# SOC_Power.net
KiCad netlist of a schematic drawn in Altium Designer
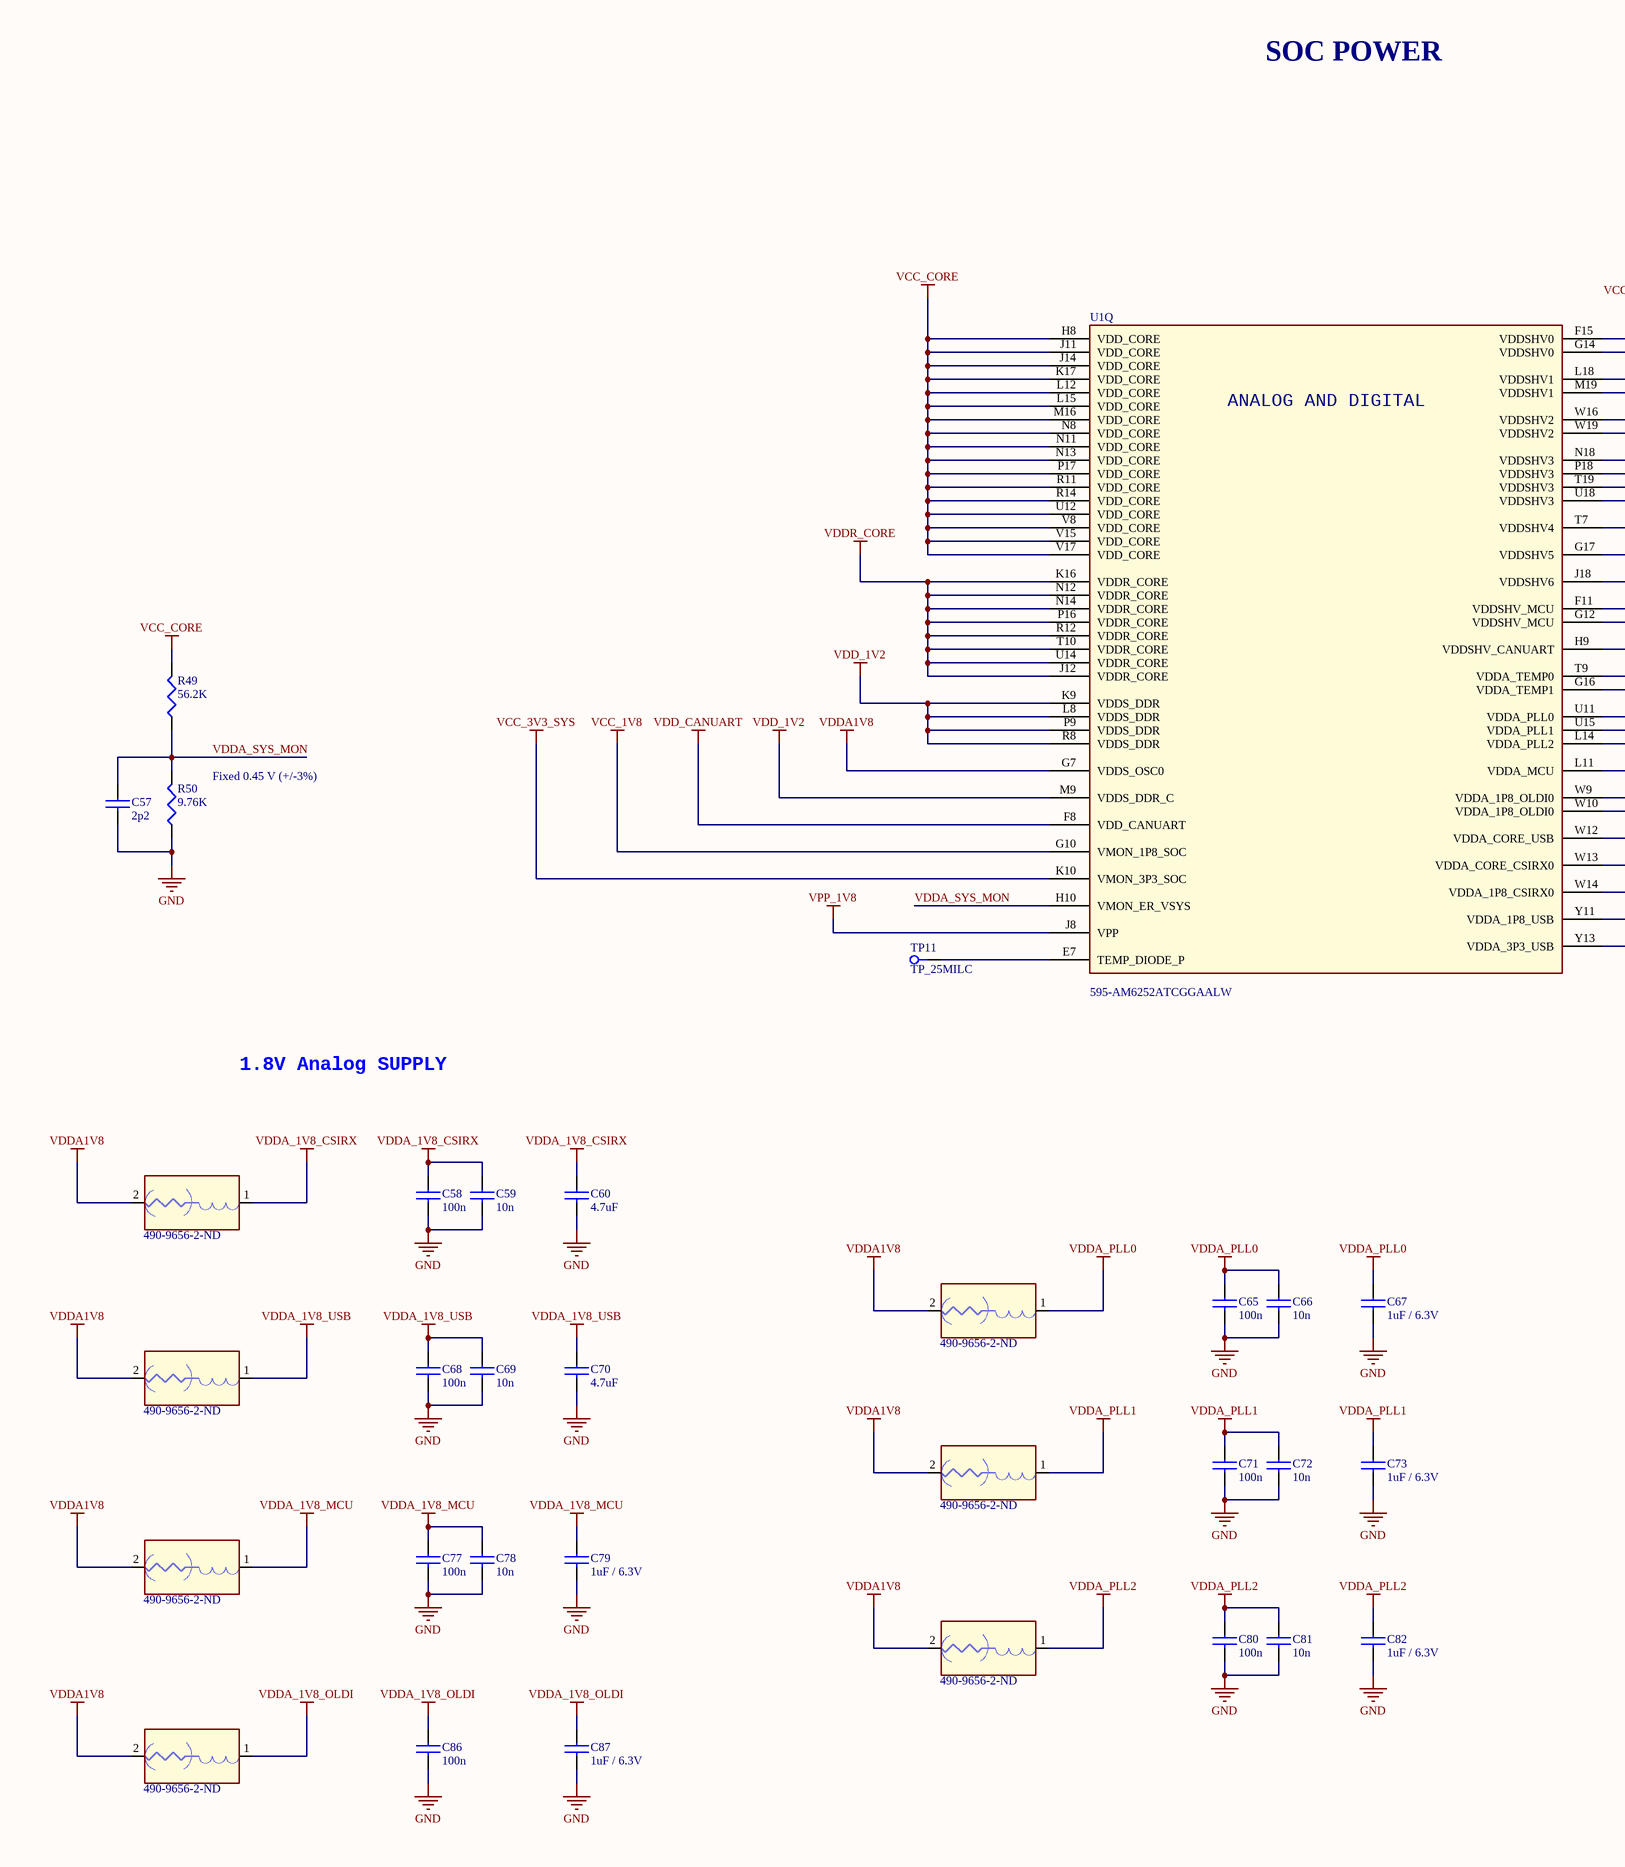
[diagram p0: SOC Power.SchDoc, left]
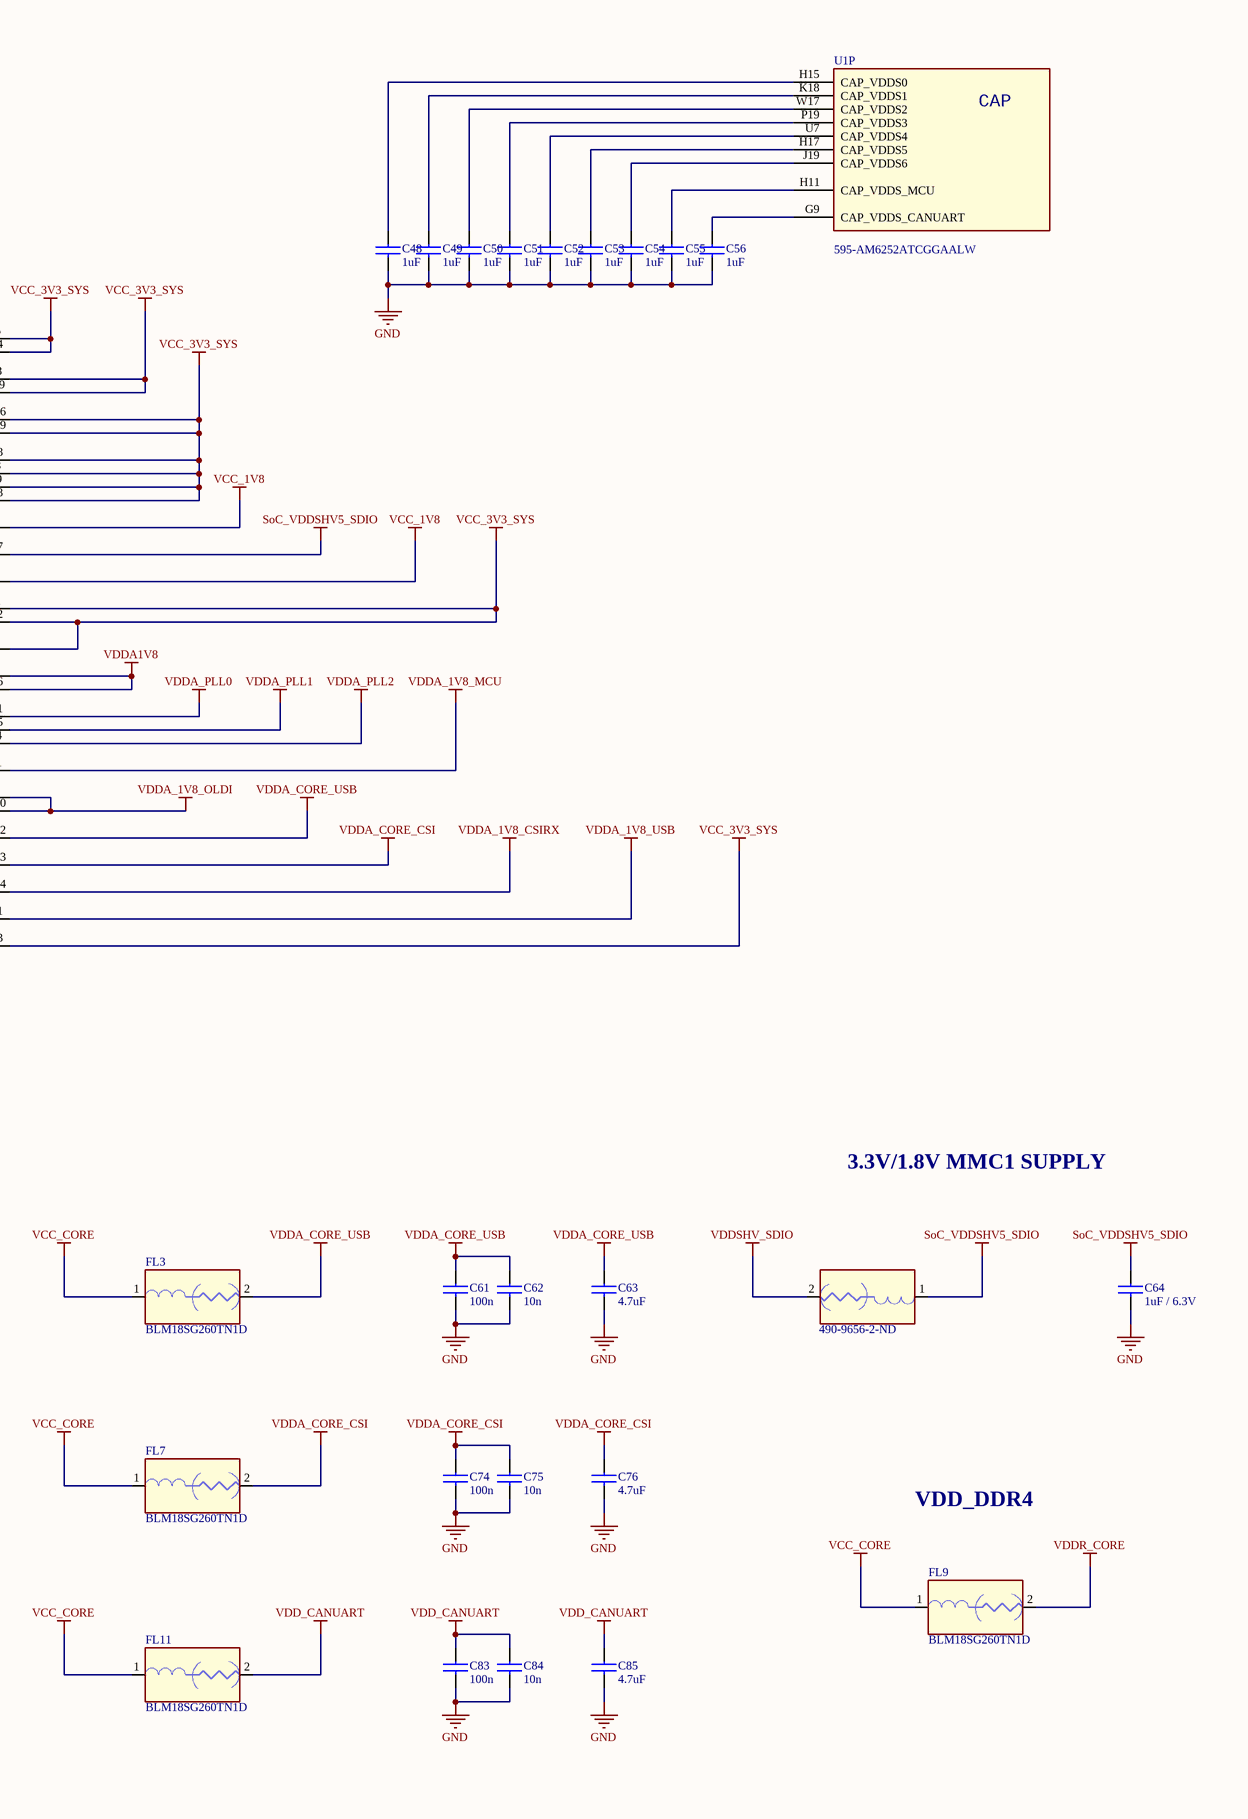
[diagram p1: SOC Power.SchDoc, right]

(export (version "E")
  (design (tool "Eeschema 10.0.6"))
  (components
    (comp (ref "C48")
      (value "1uF")
      (footprint "C0201")
      (description "CAP CER 1UF 6.3V X5R 0201")
      (fields
        (field (name "MANUFACTURER") "Samsung")
        (field (name "MANUFACTURER PART NUMBER") "CL03A105KQ3CSNC")
      )
      (libsource (lib "Schlib AM625") (part "CL03A105KQ3CSNC"))
    )
    (comp (ref "C49")
      (value "1uF")
      (footprint "C0201")
      (description "CAP CER 1UF 6.3V X5R 0201")
      (fields
        (field (name "MANUFACTURER") "Samsung")
        (field (name "MANUFACTURER PART NUMBER") "CL03A105KQ3CSNC")
      )
      (libsource (lib "Schlib AM625") (part "CL03A105KQ3CSNC"))
    )
    (comp (ref "C50")
      (value "1uF")
      (footprint "C0201")
      (description "CAP CER 1UF 6.3V X5R 0201")
      (fields
        (field (name "MANUFACTURER") "Samsung")
        (field (name "MANUFACTURER PART NUMBER") "CL03A105KQ3CSNC")
      )
      (libsource (lib "Schlib AM625") (part "CL03A105KQ3CSNC"))
    )
    (comp (ref "C51")
      (value "1uF")
      (footprint "C0201")
      (description "CAP CER 1UF 6.3V X5R 0201")
      (fields
        (field (name "MANUFACTURER") "Samsung")
        (field (name "MANUFACTURER PART NUMBER") "CL03A105KQ3CSNC")
      )
      (libsource (lib "Schlib AM625") (part "CL03A105KQ3CSNC"))
    )
    (comp (ref "C52")
      (value "1uF")
      (footprint "C0201")
      (description "CAP CER 1UF 6.3V X5R 0201")
      (fields
        (field (name "MANUFACTURER") "Samsung")
        (field (name "MANUFACTURER PART NUMBER") "CL03A105KQ3CSNC")
      )
      (libsource (lib "Schlib AM625") (part "CL03A105KQ3CSNC"))
    )
    (comp (ref "C53")
      (value "1uF")
      (footprint "C0201")
      (description "CAP CER 1UF 6.3V X5R 0201")
      (fields
        (field (name "MANUFACTURER") "Samsung")
        (field (name "MANUFACTURER PART NUMBER") "CL03A105KQ3CSNC")
      )
      (libsource (lib "Schlib AM625") (part "CL03A105KQ3CSNC"))
    )
    (comp (ref "C54")
      (value "1uF")
      (footprint "C0201")
      (description "CAP CER 1UF 6.3V X5R 0201")
      (fields
        (field (name "MANUFACTURER") "Samsung")
        (field (name "MANUFACTURER PART NUMBER") "CL03A105KQ3CSNC")
      )
      (libsource (lib "Schlib AM625") (part "CL03A105KQ3CSNC"))
    )
    (comp (ref "C55")
      (value "1uF")
      (footprint "C0201")
      (description "CAP CER 1UF 6.3V X5R 0201")
      (fields
        (field (name "MANUFACTURER") "Samsung")
        (field (name "MANUFACTURER PART NUMBER") "CL03A105KQ3CSNC")
      )
      (libsource (lib "Schlib AM625") (part "CL03A105KQ3CSNC"))
    )
    (comp (ref "C56")
      (value "1uF")
      (footprint "C0201")
      (description "CAP CER 1UF 6.3V X5R 0201")
      (fields
        (field (name "MANUFACTURER") "Samsung")
        (field (name "MANUFACTURER PART NUMBER") "CL03A105KQ3CSNC")
      )
      (libsource (lib "Schlib AM625") (part "CL03A105KQ3CSNC"))
    )
    (comp (ref "C57")
      (value "2p2")
      (footprint "C0201")
      (description "CAP CER 2.2PF 50V C0G 0201")
      (fields
        (field (name "MANUFACTURER") "TDK Corporation")
        (field (name "MANUFACTURER PART NUMBER") "C0603C0G1H2R2C030BA")
        (field (name ".CHECKED PCB") "MM")
        (field (name ".CHECKED SCH") "MM")
        (field (name ".CREATOR") "MM")
      )
      (libsource (lib "Schlib AM625") (part "C0603C0G1H2R2C030BA"))
    )
    (comp (ref "C58")
      (value "100n")
      (footprint "C0201")
      (description "CAP CER 0.1UF 16V 10% X5R 0201")
      (fields
        (field (name "MANUFACTURER") "TDK Corporation")
        (field (name "MANUFACTURER PART NUMBER") "C0603X5R1C104K030BC")
        (field (name ".CREATOR") "MM")
        (field (name ".CHECKED PCB") "MM")
        (field (name ".CHECKED SCH") "MM")
      )
      (libsource (lib "Schlib AM625") (part "C0603X5R1C104K030BC"))
    )
    (comp (ref "C59")
      (value "10n")
      (footprint "C0201")
      (description "CAP CER .01UF 16V 10% X5R 0201")
      (fields
        (field (name "MANUFACTURER") "TDK Corporation")
        (field (name "MANUFACTURER PART NUMBER") "C0603X5R1C103K030BA")
        (field (name ".CREATOR") "MM")
        (field (name ".CHECKED PCB") "MM")
        (field (name ".CHECKED SCH") "MM")
      )
      (libsource (lib "Schlib AM625") (part "C0603X5R1C103K030BA"))
    )
    (comp (ref "C60")
      (value "4.7uF")
      (footprint "C0201")
      (description "CAP CER 4.7UF 6.3V X5R 0201")
      (fields
        (field (name "MANUFACTURER") "Murata")
        (field (name "MANUFACTURER PART NUMBER") "GRM035R60J475ME15D")
      )
      (libsource (lib "Schlib AM625") (part "GRM035R60J475ME15D"))
    )
    (comp (ref "C61")
      (value "100n")
      (footprint "C0201")
      (description "CAP CER 0.1UF 16V 10% X5R 0201")
      (fields
        (field (name "MANUFACTURER") "TDK Corporation")
        (field (name "MANUFACTURER PART NUMBER") "C0603X5R1C104K030BC")
        (field (name ".CREATOR") "MM")
        (field (name ".CHECKED PCB") "MM")
        (field (name ".CHECKED SCH") "MM")
      )
      (libsource (lib "Schlib AM625") (part "C0603X5R1C104K030BC"))
    )
    (comp (ref "C62")
      (value "10n")
      (footprint "C0201")
      (description "CAP CER .01UF 16V 10% X5R 0201")
      (fields
        (field (name "MANUFACTURER") "TDK Corporation")
        (field (name "MANUFACTURER PART NUMBER") "C0603X5R1C103K030BA")
        (field (name ".CREATOR") "MM")
        (field (name ".CHECKED PCB") "MM")
        (field (name ".CHECKED SCH") "MM")
      )
      (libsource (lib "Schlib AM625") (part "C0603X5R1C103K030BA"))
    )
    (comp (ref "C63")
      (value "4.7uF")
      (footprint "C0201")
      (description "CAP CER 4.7UF 6.3V X5R 0201")
      (fields
        (field (name "MANUFACTURER") "Murata")
        (field (name "MANUFACTURER PART NUMBER") "GRM035R60J475ME15D")
      )
      (libsource (lib "Schlib AM625") (part "GRM035R60J475ME15D"))
    )
    (comp (ref "C64")
      (value "1uF / 6.3V")
      (footprint "C0201")
      (description "CAP CER 1UF 6.3V X5R 0201")
      (fields
        (field (name "MANUFACTURER") "Samsung")
        (field (name "MANUFACTURER PART NUMBER") "CL03A105KQ3CSNC")
      )
      (libsource (lib "Schlib AM625") (part "CL03A105KQ3CSNC"))
    )
    (comp (ref "C65")
      (value "100n")
      (footprint "C0201")
      (description "CAP CER 0.1UF 16V 10% X5R 0201")
      (fields
        (field (name "MANUFACTURER") "TDK Corporation")
        (field (name "MANUFACTURER PART NUMBER") "C0603X5R1C104K030BC")
        (field (name ".CREATOR") "MM")
        (field (name ".CHECKED PCB") "MM")
        (field (name ".CHECKED SCH") "MM")
      )
      (libsource (lib "Schlib AM625") (part "C0603X5R1C104K030BC"))
    )
    (comp (ref "C66")
      (value "10n")
      (footprint "C0201")
      (description "CAP CER .01UF 16V 10% X5R 0201")
      (fields
        (field (name "MANUFACTURER") "TDK Corporation")
        (field (name "MANUFACTURER PART NUMBER") "C0603X5R1C103K030BA")
        (field (name ".CREATOR") "MM")
        (field (name ".CHECKED PCB") "MM")
        (field (name ".CHECKED SCH") "MM")
      )
      (libsource (lib "Schlib AM625") (part "C0603X5R1C103K030BA"))
    )
    (comp (ref "C67")
      (value "1uF / 6.3V")
      (footprint "C0201")
      (description "CAP CER 1UF 6.3V X5R 0201")
      (fields
        (field (name "MANUFACTURER") "Samsung")
        (field (name "MANUFACTURER PART NUMBER") "CL03A105KQ3CSNC")
      )
      (libsource (lib "Schlib AM625") (part "CL03A105KQ3CSNC"))
    )
    (comp (ref "C68")
      (value "100n")
      (footprint "C0201")
      (description "CAP CER 0.1UF 16V 10% X5R 0201")
      (fields
        (field (name "MANUFACTURER") "TDK Corporation")
        (field (name "MANUFACTURER PART NUMBER") "C0603X5R1C104K030BC")
        (field (name ".CREATOR") "MM")
        (field (name ".CHECKED PCB") "MM")
        (field (name ".CHECKED SCH") "MM")
      )
      (libsource (lib "Schlib AM625") (part "C0603X5R1C104K030BC"))
    )
    (comp (ref "C69")
      (value "10n")
      (footprint "C0201")
      (description "CAP CER .01UF 16V 10% X5R 0201")
      (fields
        (field (name "MANUFACTURER") "TDK Corporation")
        (field (name "MANUFACTURER PART NUMBER") "C0603X5R1C103K030BA")
        (field (name ".CREATOR") "MM")
        (field (name ".CHECKED PCB") "MM")
        (field (name ".CHECKED SCH") "MM")
      )
      (libsource (lib "Schlib AM625") (part "C0603X5R1C103K030BA"))
    )
    (comp (ref "C70")
      (value "4.7uF")
      (footprint "C0201")
      (description "CAP CER 4.7UF 6.3V X5R 0201")
      (fields
        (field (name "MANUFACTURER") "Murata")
        (field (name "MANUFACTURER PART NUMBER") "GRM035R60J475ME15D")
      )
      (libsource (lib "Schlib AM625") (part "GRM035R60J475ME15D"))
    )
    (comp (ref "C71")
      (value "100n")
      (footprint "C0201")
      (description "CAP CER 0.1UF 16V 10% X5R 0201")
      (fields
        (field (name "MANUFACTURER") "TDK Corporation")
        (field (name "MANUFACTURER PART NUMBER") "C0603X5R1C104K030BC")
        (field (name ".CREATOR") "MM")
        (field (name ".CHECKED PCB") "MM")
        (field (name ".CHECKED SCH") "MM")
      )
      (libsource (lib "Schlib AM625") (part "C0603X5R1C104K030BC"))
    )
    (comp (ref "C72")
      (value "10n")
      (footprint "C0201")
      (description "CAP CER .01UF 16V 10% X5R 0201")
      (fields
        (field (name "MANUFACTURER") "TDK Corporation")
        (field (name "MANUFACTURER PART NUMBER") "C0603X5R1C103K030BA")
        (field (name ".CREATOR") "MM")
        (field (name ".CHECKED PCB") "MM")
        (field (name ".CHECKED SCH") "MM")
      )
      (libsource (lib "Schlib AM625") (part "C0603X5R1C103K030BA"))
    )
    (comp (ref "C73")
      (value "1uF / 6.3V")
      (footprint "C0201")
      (description "CAP CER 1UF 6.3V X5R 0201")
      (fields
        (field (name "MANUFACTURER") "Samsung")
        (field (name "MANUFACTURER PART NUMBER") "CL03A105KQ3CSNC")
      )
      (libsource (lib "Schlib AM625") (part "CL03A105KQ3CSNC"))
    )
    (comp (ref "C74")
      (value "100n")
      (footprint "C0201")
      (description "CAP CER 0.1UF 16V 10% X5R 0201")
      (fields
        (field (name "MANUFACTURER") "TDK Corporation")
        (field (name "MANUFACTURER PART NUMBER") "C0603X5R1C104K030BC")
        (field (name ".CREATOR") "MM")
        (field (name ".CHECKED PCB") "MM")
        (field (name ".CHECKED SCH") "MM")
      )
      (libsource (lib "Schlib AM625") (part "C0603X5R1C104K030BC"))
    )
    (comp (ref "C75")
      (value "10n")
      (footprint "C0201")
      (description "CAP CER .01UF 16V 10% X5R 0201")
      (fields
        (field (name "MANUFACTURER") "TDK Corporation")
        (field (name "MANUFACTURER PART NUMBER") "C0603X5R1C103K030BA")
        (field (name ".CREATOR") "MM")
        (field (name ".CHECKED PCB") "MM")
        (field (name ".CHECKED SCH") "MM")
      )
      (libsource (lib "Schlib AM625") (part "C0603X5R1C103K030BA"))
    )
    (comp (ref "C76")
      (value "4.7uF")
      (footprint "C0201")
      (description "CAP CER 4.7UF 6.3V X5R 0201")
      (fields
        (field (name "MANUFACTURER") "Murata")
        (field (name "MANUFACTURER PART NUMBER") "GRM035R60J475ME15D")
      )
      (libsource (lib "Schlib AM625") (part "GRM035R60J475ME15D"))
    )
    (comp (ref "C77")
      (value "100n")
      (footprint "C0201")
      (description "CAP CER 0.1UF 16V 10% X5R 0201")
      (fields
        (field (name "MANUFACTURER") "TDK Corporation")
        (field (name "MANUFACTURER PART NUMBER") "C0603X5R1C104K030BC")
        (field (name ".CREATOR") "MM")
        (field (name ".CHECKED PCB") "MM")
        (field (name ".CHECKED SCH") "MM")
      )
      (libsource (lib "Schlib AM625") (part "C0603X5R1C104K030BC"))
    )
    (comp (ref "C78")
      (value "10n")
      (footprint "C0201")
      (description "CAP CER .01UF 16V 10% X5R 0201")
      (fields
        (field (name "MANUFACTURER") "TDK Corporation")
        (field (name "MANUFACTURER PART NUMBER") "C0603X5R1C103K030BA")
        (field (name ".CREATOR") "MM")
        (field (name ".CHECKED PCB") "MM")
        (field (name ".CHECKED SCH") "MM")
      )
      (libsource (lib "Schlib AM625") (part "C0603X5R1C103K030BA"))
    )
    (comp (ref "C79")
      (value "1uF / 6.3V")
      (footprint "C0201")
      (description "CAP CER 1UF 6.3V X5R 0201")
      (fields
        (field (name "MANUFACTURER") "Samsung")
        (field (name "MANUFACTURER PART NUMBER") "CL03A105KQ3CSNC")
      )
      (libsource (lib "Schlib AM625") (part "CL03A105KQ3CSNC"))
    )
    (comp (ref "C80")
      (value "100n")
      (footprint "C0201")
      (description "CAP CER 0.1UF 16V 10% X5R 0201")
      (fields
        (field (name "MANUFACTURER") "TDK Corporation")
        (field (name "MANUFACTURER PART NUMBER") "C0603X5R1C104K030BC")
        (field (name ".CREATOR") "MM")
        (field (name ".CHECKED PCB") "MM")
        (field (name ".CHECKED SCH") "MM")
      )
      (libsource (lib "Schlib AM625") (part "C0603X5R1C104K030BC"))
    )
    (comp (ref "C81")
      (value "10n")
      (footprint "C0201")
      (description "CAP CER .01UF 16V 10% X5R 0201")
      (fields
        (field (name "MANUFACTURER") "TDK Corporation")
        (field (name "MANUFACTURER PART NUMBER") "C0603X5R1C103K030BA")
        (field (name ".CREATOR") "MM")
        (field (name ".CHECKED PCB") "MM")
        (field (name ".CHECKED SCH") "MM")
      )
      (libsource (lib "Schlib AM625") (part "C0603X5R1C103K030BA"))
    )
    (comp (ref "C82")
      (value "1uF / 6.3V")
      (footprint "C0201")
      (description "CAP CER 1UF 6.3V X5R 0201")
      (fields
        (field (name "MANUFACTURER") "Samsung")
        (field (name "MANUFACTURER PART NUMBER") "CL03A105KQ3CSNC")
      )
      (libsource (lib "Schlib AM625") (part "CL03A105KQ3CSNC"))
    )
    (comp (ref "C83")
      (value "100n")
      (footprint "C0201")
      (description "CAP CER 0.1UF 16V 10% X5R 0201")
      (fields
        (field (name "MANUFACTURER") "TDK Corporation")
        (field (name "MANUFACTURER PART NUMBER") "C0603X5R1C104K030BC")
        (field (name ".CREATOR") "MM")
        (field (name ".CHECKED PCB") "MM")
        (field (name ".CHECKED SCH") "MM")
      )
      (libsource (lib "Schlib AM625") (part "C0603X5R1C104K030BC"))
    )
    (comp (ref "C84")
      (value "10n")
      (footprint "C0201")
      (description "CAP CER .01UF 16V 10% X5R 0201")
      (fields
        (field (name "MANUFACTURER") "TDK Corporation")
        (field (name "MANUFACTURER PART NUMBER") "C0603X5R1C103K030BA")
        (field (name ".CREATOR") "MM")
        (field (name ".CHECKED PCB") "MM")
        (field (name ".CHECKED SCH") "MM")
      )
      (libsource (lib "Schlib AM625") (part "C0603X5R1C103K030BA"))
    )
    (comp (ref "C85")
      (value "4.7uF")
      (footprint "C0201")
      (description "CAP CER 4.7UF 6.3V X5R 0201")
      (fields
        (field (name "MANUFACTURER") "Murata")
        (field (name "MANUFACTURER PART NUMBER") "GRM035R60J475ME15D")
      )
      (libsource (lib "Schlib AM625") (part "GRM035R60J475ME15D"))
    )
    (comp (ref "C86")
      (value "100n")
      (footprint "C0201")
      (description "CAP CER 0.1UF 16V 10% X5R 0201")
      (fields
        (field (name "MANUFACTURER") "TDK Corporation")
        (field (name "MANUFACTURER PART NUMBER") "C0603X5R1C104K030BC")
        (field (name ".CREATOR") "MM")
        (field (name ".CHECKED PCB") "MM")
        (field (name ".CHECKED SCH") "MM")
      )
      (libsource (lib "Schlib AM625") (part "C0603X5R1C104K030BC"))
    )
    (comp (ref "C87")
      (value "1uF / 6.3V")
      (footprint "C0201")
      (description "CAP CER 1UF 6.3V X5R 0201")
      (fields
        (field (name "MANUFACTURER") "Samsung")
        (field (name "MANUFACTURER PART NUMBER") "CL03A105KQ3CSNC")
      )
      (libsource (lib "Schlib AM625") (part "CL03A105KQ3CSNC"))
    )
    (comp (ref "FL2")
      (value "BLM15PX121SN1D")
      (footprint "NFZ15SG152SN10B")
      (description "FERRITE BEAD 120 OHM 0402 1LN")
      (fields
        (field (name "MANUFACTURER") "Murata")
        (field (name "TOLERANCE") "25%")
        (field (name "SUPPLIER PART NUMBER 1") "490-9656-2-ND")
      )
      (libsource (lib "Schlib AM625") (part "BLM15PX121SN1D"))
    )
    (comp (ref "FL3")
      (value "BLM18SG260TN1D")
      (footprint "BLM18EG101TH1D")
      (description "FERRITE BEAD 26 OHM 0603 1LN")
      (fields (field (name "MANUFACTURER") "Murata") (field (name "TOLERANCE") "25%"))
      (libsource (lib "Schlib AM625") (part "BLM18SG260TN1D"))
    )
    (comp (ref "FL4")
      (value "BLM15PX121SN1D")
      (footprint "NFZ15SG152SN10B")
      (description "FERRITE BEAD 120 OHM 0402 1LN")
      (fields
        (field (name "MANUFACTURER") "Murata")
        (field (name "TOLERANCE") "25%")
        (field (name "SUPPLIER PART NUMBER 1") "490-9656-2-ND")
      )
      (libsource (lib "Schlib AM625") (part "BLM15PX121SN1D"))
    )
    (comp (ref "FL5")
      (value "BLM15PX121SN1D")
      (footprint "NFZ15SG152SN10B")
      (description "FERRITE BEAD 120 OHM 0402 1LN")
      (fields
        (field (name "MANUFACTURER") "Murata")
        (field (name "TOLERANCE") "25%")
        (field (name "SUPPLIER PART NUMBER 1") "490-9656-2-ND")
      )
      (libsource (lib "Schlib AM625") (part "BLM15PX121SN1D"))
    )
    (comp (ref "FL6")
      (value "BLM15PX121SN1D")
      (footprint "NFZ15SG152SN10B")
      (description "FERRITE BEAD 120 OHM 0402 1LN")
      (fields
        (field (name "MANUFACTURER") "Murata")
        (field (name "TOLERANCE") "25%")
        (field (name "SUPPLIER PART NUMBER 1") "490-9656-2-ND")
      )
      (libsource (lib "Schlib AM625") (part "BLM15PX121SN1D"))
    )
    (comp (ref "FL7")
      (value "BLM18SG260TN1D")
      (footprint "BLM18EG101TH1D")
      (description "FERRITE BEAD 26 OHM 0603 1LN")
      (fields (field (name "MANUFACTURER") "Murata") (field (name "TOLERANCE") "25%"))
      (libsource (lib "Schlib AM625") (part "BLM18SG260TN1D"))
    )
    (comp (ref "FL8")
      (value "BLM15PX121SN1D")
      (footprint "NFZ15SG152SN10B")
      (description "FERRITE BEAD 120 OHM 0402 1LN")
      (fields
        (field (name "MANUFACTURER") "Murata")
        (field (name "TOLERANCE") "25%")
        (field (name "SUPPLIER PART NUMBER 1") "490-9656-2-ND")
      )
      (libsource (lib "Schlib AM625") (part "BLM15PX121SN1D"))
    )
    (comp (ref "FL9")
      (value "BLM18SG260TN1D")
      (footprint "BLM18EG101TH1D")
      (description "FERRITE BEAD 26 OHM 0603 1LN")
      (fields (field (name "MANUFACTURER") "Murata") (field (name "TOLERANCE") "25%"))
      (libsource (lib "Schlib AM625") (part "BLM18SG260TN1D"))
    )
    (comp (ref "FL10")
      (value "BLM15PX121SN1D")
      (footprint "NFZ15SG152SN10B")
      (description "FERRITE BEAD 120 OHM 0402 1LN")
      (fields
        (field (name "MANUFACTURER") "Murata")
        (field (name "TOLERANCE") "25%")
        (field (name "SUPPLIER PART NUMBER 1") "490-9656-2-ND")
      )
      (libsource (lib "Schlib AM625") (part "BLM15PX121SN1D"))
    )
    (comp (ref "FL11")
      (value "BLM18SG260TN1D")
      (footprint "BLM18EG101TH1D")
      (description "FERRITE BEAD 26 OHM 0603 1LN")
      (fields (field (name "MANUFACTURER") "Murata") (field (name "TOLERANCE") "25%"))
      (libsource (lib "Schlib AM625") (part "BLM18SG260TN1D"))
    )
    (comp (ref "FL12")
      (value "BLM15PX121SN1D")
      (footprint "NFZ15SG152SN10B")
      (description "FERRITE BEAD 120 OHM 0402 1LN")
      (fields
        (field (name "MANUFACTURER") "Murata")
        (field (name "TOLERANCE") "25%")
        (field (name "SUPPLIER PART NUMBER 1") "490-9656-2-ND")
      )
      (libsource (lib "Schlib AM625") (part "BLM15PX121SN1D"))
    )
    (comp (ref "FL13")
      (value "BLM15PX121SN1D")
      (footprint "NFZ15SG152SN10B")
      (description "FERRITE BEAD 120 OHM 0402 1LN")
      (fields
        (field (name "MANUFACTURER") "Murata")
        (field (name "TOLERANCE") "25%")
        (field (name "SUPPLIER PART NUMBER 1") "490-9656-2-ND")
      )
      (libsource (lib "Schlib AM625") (part "BLM15PX121SN1D"))
    )
    (comp (ref "R49")
      (value "56.2K")
      (footprint "R0201")
      (description "RES 56.2K OHM 1% 1/20W 0201")
      (fields
        (field (name "MANUFACTURER") "Yageo")
        (field (name "MANUFACTURER PART NUMBER") "RC0201FR-0756K2L")
      )
      (libsource (lib "Schlib AM625") (part "RC0201FR-0756K2L"))
    )
    (comp (ref "R50")
      (value "9.76K")
      (footprint "R0201")
      (description "RES 9.76K OHM 1% 1/20W 0201")
      (fields
        (field (name "MANUFACTURER") "Yageo")
        (field (name "MANUFACTURER PART NUMBER") "RC0201FR-079K76L")
      )
      (libsource (lib "Schlib AM625") (part "RC0201FR-079K76L"))
    )
    (comp (ref "TP11")
      (value "TP_25MILC")
      (footprint "TP_25C")
      (description "Test Point 25mil")
      (libsource (lib "Schlib AM625") (part "TP_25MILC"))
    )
    (comp (ref "U1")
      (value "AM62-EVM_BGA425")
      (footprint "BGA425C50P25X25_1300X1300X89")
      (description "ARM® Cortex®-A53 Microprocessor IC Sitara™ 2 Core, 64-Bit 1.4GHz 425-FCCSP (13x13)")
      (fields
        (field (name "MANUFACTURER") "Texas Instruments")
        (field (name "MANUFACTURER PART NUMBER") "AM6252ATCGGAALW")
        (field (name "SUPPLIER PART NUMBER 1") "595-AM6252ATCGGAALW")
      )
      (libsource (lib "Schlib AM625") (part "AM62-EVM_BGA425"))
    )
  )
  (nets
    (net (code "1") (name "/VDDA_SYS_MON") (class "Default")
      (node (ref "C57") (pin "1") (pinfunction "1_1") (pintype "passive"))
      (node (ref "R49") (pin "1") (pinfunction "1_1") (pintype "passive"))
      (node (ref "R50") (pin "2") (pinfunction "2_2") (pintype "passive"))
      (node (ref "U1") (pin "H10") (pinfunction "VMON_ER_VSYS_H10") (pintype "power_in"))
    )
    (net (code "2") (name "GND") (class "Default")
      (node (ref "C48") (pin "2") (pinfunction "2_2") (pintype "passive"))
      (node (ref "C49") (pin "2") (pinfunction "2_2") (pintype "passive"))
      (node (ref "C50") (pin "2") (pinfunction "2_2") (pintype "passive"))
      (node (ref "C51") (pin "2") (pinfunction "2_2") (pintype "passive"))
      (node (ref "C52") (pin "2") (pinfunction "2_2") (pintype "passive"))
      (node (ref "C53") (pin "2") (pinfunction "2_2") (pintype "passive"))
      (node (ref "C54") (pin "2") (pinfunction "2_2") (pintype "passive"))
      (node (ref "C55") (pin "2") (pinfunction "2_2") (pintype "passive"))
      (node (ref "C56") (pin "2") (pinfunction "2_2") (pintype "passive"))
      (node (ref "C57") (pin "2") (pinfunction "2_2") (pintype "passive"))
      (node (ref "C58") (pin "2") (pinfunction "2_2") (pintype "passive"))
      (node (ref "C59") (pin "2") (pinfunction "2_2") (pintype "passive"))
      (node (ref "C60") (pin "2") (pinfunction "2_2") (pintype "passive"))
      (node (ref "C61") (pin "2") (pinfunction "2_2") (pintype "passive"))
      (node (ref "C62") (pin "2") (pinfunction "2_2") (pintype "passive"))
      (node (ref "C63") (pin "2") (pinfunction "2_2") (pintype "passive"))
      (node (ref "C64") (pin "2") (pinfunction "2_2") (pintype "passive"))
      (node (ref "C65") (pin "2") (pinfunction "2_2") (pintype "passive"))
      (node (ref "C66") (pin "2") (pinfunction "2_2") (pintype "passive"))
      (node (ref "C67") (pin "2") (pinfunction "2_2") (pintype "passive"))
      (node (ref "C68") (pin "2") (pinfunction "2_2") (pintype "passive"))
      (node (ref "C69") (pin "2") (pinfunction "2_2") (pintype "passive"))
      (node (ref "C70") (pin "2") (pinfunction "2_2") (pintype "passive"))
      (node (ref "C71") (pin "2") (pinfunction "2_2") (pintype "passive"))
      (node (ref "C72") (pin "2") (pinfunction "2_2") (pintype "passive"))
      (node (ref "C73") (pin "2") (pinfunction "2_2") (pintype "passive"))
      (node (ref "C74") (pin "2") (pinfunction "2_2") (pintype "passive"))
      (node (ref "C75") (pin "2") (pinfunction "2_2") (pintype "passive"))
      (node (ref "C76") (pin "2") (pinfunction "2_2") (pintype "passive"))
      (node (ref "C77") (pin "2") (pinfunction "2_2") (pintype "passive"))
      (node (ref "C78") (pin "2") (pinfunction "2_2") (pintype "passive"))
      (node (ref "C79") (pin "2") (pinfunction "2_2") (pintype "passive"))
      (node (ref "C80") (pin "2") (pinfunction "2_2") (pintype "passive"))
      (node (ref "C81") (pin "2") (pinfunction "2_2") (pintype "passive"))
      (node (ref "C82") (pin "2") (pinfunction "2_2") (pintype "passive"))
      (node (ref "C83") (pin "2") (pinfunction "2_2") (pintype "passive"))
      (node (ref "C84") (pin "2") (pinfunction "2_2") (pintype "passive"))
      (node (ref "C85") (pin "2") (pinfunction "2_2") (pintype "passive"))
      (node (ref "C86") (pin "2") (pinfunction "2_2") (pintype "passive"))
      (node (ref "C87") (pin "2") (pinfunction "2_2") (pintype "passive"))
      (node (ref "R50") (pin "1") (pinfunction "1_1") (pintype "passive"))
    )
    (net (code "3") (name "Net-(U1P-CAP_VDDS0)") (class "Default")
      (node (ref "C48") (pin "1") (pinfunction "1_1") (pintype "passive"))
      (node (ref "U1") (pin "H15") (pinfunction "CAP_VDDS0_H15") (pintype "power_in"))
    )
    (net (code "4") (name "Net-(U1P-CAP_VDDS1)") (class "Default")
      (node (ref "C49") (pin "1") (pinfunction "1_1") (pintype "passive"))
      (node (ref "U1") (pin "K18") (pinfunction "CAP_VDDS1_K18") (pintype "power_in"))
    )
    (net (code "5") (name "Net-(U1P-CAP_VDDS2)") (class "Default")
      (node (ref "C50") (pin "1") (pinfunction "1_1") (pintype "passive"))
      (node (ref "U1") (pin "W17") (pinfunction "CAP_VDDS2_W17") (pintype "power_in"))
    )
    (net (code "6") (name "Net-(U1P-CAP_VDDS3)") (class "Default")
      (node (ref "C51") (pin "1") (pinfunction "1_1") (pintype "passive"))
      (node (ref "U1") (pin "P19") (pinfunction "CAP_VDDS3_P19") (pintype "power_in"))
    )
    (net (code "7") (name "Net-(U1P-CAP_VDDS4)") (class "Default")
      (node (ref "C52") (pin "1") (pinfunction "1_1") (pintype "passive"))
      (node (ref "U1") (pin "U7") (pinfunction "CAP_VDDS4_U7") (pintype "power_in"))
    )
    (net (code "8") (name "Net-(U1P-CAP_VDDS5)") (class "Default")
      (node (ref "C53") (pin "1") (pinfunction "1_1") (pintype "passive"))
      (node (ref "U1") (pin "H17") (pinfunction "CAP_VDDS5_H17") (pintype "power_in"))
    )
    (net (code "9") (name "Net-(U1P-CAP_VDDS6)") (class "Default")
      (node (ref "C54") (pin "1") (pinfunction "1_1") (pintype "passive"))
      (node (ref "U1") (pin "J19") (pinfunction "CAP_VDDS6_J19") (pintype "power_in"))
    )
    (net (code "10") (name "Net-(U1P-CAP_VDDS_CANUART)") (class "Default")
      (node (ref "C56") (pin "1") (pinfunction "1_1") (pintype "passive"))
      (node (ref "U1") (pin "G9") (pinfunction "CAP_VDDS_CANUART_G9") (pintype "power_in"))
    )
    (net (code "11") (name "Net-(U1P-CAP_VDDS_MCU)") (class "Default")
      (node (ref "C55") (pin "1") (pinfunction "1_1") (pintype "passive"))
      (node (ref "U1") (pin "H11") (pinfunction "CAP_VDDS_MCU_H11") (pintype "power_in"))
    )
    (net (code "12") (name "Net-(U1Q-TEMP_DIODE_P)") (class "Default")
      (node (ref "TP11") (pin "1") (pinfunction "1_1") (pintype "passive"))
      (node (ref "U1") (pin "E7") (pinfunction "TEMP_DIODE_P_E7") (pintype "power_in"))
    )
    (net (code "13") (name "SoC_VDDSHV5_SDIO") (class "Default")
      (node (ref "C64") (pin "1") (pinfunction "1_1") (pintype "passive"))
      (node (ref "FL4") (pin "1") (pinfunction "1_1") (pintype "passive"))
      (node (ref "U1") (pin "G17") (pinfunction "VDDSHV5_G17") (pintype "power_in"))
    )
    (net (code "14") (name "VCC_1V8") (class "Default")
      (node (ref "U1") (pin "G10") (pinfunction "VMON_1P8_SOC_G10") (pintype "power_in"))
      (node (ref "U1") (pin "J18") (pinfunction "VDDSHV6_J18") (pintype "power_in"))
      (node (ref "U1") (pin "T7") (pinfunction "VDDSHV4_T7") (pintype "power_in"))
    )
    (net (code "15") (name "VCC_3V3_SYS") (class "Default")
      (node (ref "U1") (pin "F11") (pinfunction "VDDSHV_MCU_F11") (pintype "power_in"))
      (node (ref "U1") (pin "F15") (pinfunction "VDDSHV0_F15") (pintype "power_in"))
      (node (ref "U1") (pin "G12") (pinfunction "VDDSHV_MCU_G12") (pintype "power_in"))
      (node (ref "U1") (pin "G14") (pinfunction "VDDSHV0_G14") (pintype "power_in"))
      (node (ref "U1") (pin "H9") (pinfunction "VDDSHV_CANUART_H9") (pintype "power_in"))
      (node (ref "U1") (pin "K10") (pinfunction "VMON_3P3_SOC_K10") (pintype "power_in"))
      (node (ref "U1") (pin "L18") (pinfunction "VDDSHV1_L18") (pintype "power_in"))
      (node (ref "U1") (pin "M19") (pinfunction "VDDSHV1_M19") (pintype "power_in"))
      (node (ref "U1") (pin "N18") (pinfunction "VDDSHV3_N18") (pintype "power_in"))
      (node (ref "U1") (pin "P18") (pinfunction "VDDSHV3_P18") (pintype "power_in"))
      (node (ref "U1") (pin "T19") (pinfunction "VDDSHV3_T19") (pintype "power_in"))
      (node (ref "U1") (pin "U18") (pinfunction "VDDSHV3_U18") (pintype "power_in"))
      (node (ref "U1") (pin "W16") (pinfunction "VDDSHV2_W16") (pintype "power_in"))
      (node (ref "U1") (pin "W19") (pinfunction "VDDSHV2_W19") (pintype "power_in"))
      (node (ref "U1") (pin "Y13") (pinfunction "VDDA_3P3_USB_Y13") (pintype "power_in"))
    )
    (net (code "16") (name "VCC_CORE") (class "Default")
      (node (ref "FL11") (pin "1") (pinfunction "1_1") (pintype "passive"))
      (node (ref "FL3") (pin "1") (pinfunction "1_1") (pintype "passive"))
      (node (ref "FL7") (pin "1") (pinfunction "1_1") (pintype "passive"))
      (node (ref "FL9") (pin "1") (pinfunction "1_1") (pintype "passive"))
      (node (ref "R49") (pin "2") (pinfunction "2_2") (pintype "passive"))
      (node (ref "U1") (pin "H8") (pinfunction "VDD_CORE_H8") (pintype "power_in"))
      (node (ref "U1") (pin "J11") (pinfunction "VDD_CORE_J11") (pintype "power_in"))
      (node (ref "U1") (pin "J14") (pinfunction "VDD_CORE_J14") (pintype "power_in"))
      (node (ref "U1") (pin "K17") (pinfunction "VDD_CORE_K17") (pintype "power_in"))
      (node (ref "U1") (pin "L12") (pinfunction "VDD_CORE_L12") (pintype "power_in"))
      (node (ref "U1") (pin "L15") (pinfunction "VDD_CORE_L15") (pintype "power_in"))
      (node (ref "U1") (pin "M16") (pinfunction "VDD_CORE_M16") (pintype "power_in"))
      (node (ref "U1") (pin "N11") (pinfunction "VDD_CORE_N11") (pintype "power_in"))
      (node (ref "U1") (pin "N13") (pinfunction "VDD_CORE_N13") (pintype "power_in"))
      (node (ref "U1") (pin "N8") (pinfunction "VDD_CORE_N8") (pintype "power_in"))
      (node (ref "U1") (pin "P17") (pinfunction "VDD_CORE_P17") (pintype "power_in"))
      (node (ref "U1") (pin "R11") (pinfunction "VDD_CORE_R11") (pintype "power_in"))
      (node (ref "U1") (pin "R14") (pinfunction "VDD_CORE_R14") (pintype "power_in"))
      (node (ref "U1") (pin "U12") (pinfunction "VDD_CORE_U12") (pintype "power_in"))
      (node (ref "U1") (pin "V15") (pinfunction "VDD_CORE_V15") (pintype "power_in"))
      (node (ref "U1") (pin "V17") (pinfunction "VDD_CORE_V17") (pintype "power_in"))
      (node (ref "U1") (pin "V8") (pinfunction "VDD_CORE_V8") (pintype "power_in"))
    )
    (net (code "17") (name "VDDA1V8") (class "Default")
      (node (ref "FL10") (pin "2") (pinfunction "2_2") (pintype "passive"))
      (node (ref "FL12") (pin "2") (pinfunction "2_2") (pintype "passive"))
      (node (ref "FL13") (pin "2") (pinfunction "2_2") (pintype "passive"))
      (node (ref "FL2") (pin "2") (pinfunction "2_2") (pintype "passive"))
      (node (ref "FL5") (pin "2") (pinfunction "2_2") (pintype "passive"))
      (node (ref "FL6") (pin "2") (pinfunction "2_2") (pintype "passive"))
      (node (ref "FL8") (pin "2") (pinfunction "2_2") (pintype "passive"))
      (node (ref "U1") (pin "G16") (pinfunction "VDDA_TEMP1_G16") (pintype "power_in"))
      (node (ref "U1") (pin "G7") (pinfunction "VDDS_OSC0_G7") (pintype "power_in"))
      (node (ref "U1") (pin "T9") (pinfunction "VDDA_TEMP0_T9") (pintype "power_in"))
    )
    (net (code "18") (name "VDDA_1V8_CSIRX") (class "Default")
      (node (ref "C58") (pin "1") (pinfunction "1_1") (pintype "passive"))
      (node (ref "C59") (pin "1") (pinfunction "1_1") (pintype "passive"))
      (node (ref "C60") (pin "1") (pinfunction "1_1") (pintype "passive"))
      (node (ref "FL2") (pin "1") (pinfunction "1_1") (pintype "passive"))
      (node (ref "U1") (pin "W14") (pinfunction "VDDA_1P8_CSIRX0_W14") (pintype "power_in"))
    )
    (net (code "19") (name "VDDA_1V8_MCU") (class "Default")
      (node (ref "C77") (pin "1") (pinfunction "1_1") (pintype "passive"))
      (node (ref "C78") (pin "1") (pinfunction "1_1") (pintype "passive"))
      (node (ref "C79") (pin "1") (pinfunction "1_1") (pintype "passive"))
      (node (ref "FL10") (pin "1") (pinfunction "1_1") (pintype "passive"))
      (node (ref "U1") (pin "L11") (pinfunction "VDDA_MCU_L11") (pintype "power_in"))
    )
    (net (code "20") (name "VDDA_1V8_OLDI") (class "Default")
      (node (ref "C86") (pin "1") (pinfunction "1_1") (pintype "passive"))
      (node (ref "C87") (pin "1") (pinfunction "1_1") (pintype "passive"))
      (node (ref "FL13") (pin "1") (pinfunction "1_1") (pintype "passive"))
      (node (ref "U1") (pin "W10") (pinfunction "VDDA_1P8_OLDI0_W10") (pintype "power_in"))
      (node (ref "U1") (pin "W9") (pinfunction "VDDA_1P8_OLDI0_W9") (pintype "power_in"))
    )
    (net (code "21") (name "VDDA_1V8_USB") (class "Default")
      (node (ref "C68") (pin "1") (pinfunction "1_1") (pintype "passive"))
      (node (ref "C69") (pin "1") (pinfunction "1_1") (pintype "passive"))
      (node (ref "C70") (pin "1") (pinfunction "1_1") (pintype "passive"))
      (node (ref "FL6") (pin "1") (pinfunction "1_1") (pintype "passive"))
      (node (ref "U1") (pin "Y11") (pinfunction "VDDA_1P8_USB_Y11") (pintype "power_in"))
    )
    (net (code "22") (name "VDDA_CORE_CSI") (class "Default")
      (node (ref "C74") (pin "1") (pinfunction "1_1") (pintype "passive"))
      (node (ref "C75") (pin "1") (pinfunction "1_1") (pintype "passive"))
      (node (ref "C76") (pin "1") (pinfunction "1_1") (pintype "passive"))
      (node (ref "FL7") (pin "2") (pinfunction "2_2") (pintype "passive"))
      (node (ref "U1") (pin "W13") (pinfunction "VDDA_CORE_CSIRX0_W13") (pintype "power_in"))
    )
    (net (code "23") (name "VDDA_CORE_USB") (class "Default")
      (node (ref "C61") (pin "1") (pinfunction "1_1") (pintype "passive"))
      (node (ref "C62") (pin "1") (pinfunction "1_1") (pintype "passive"))
      (node (ref "C63") (pin "1") (pinfunction "1_1") (pintype "passive"))
      (node (ref "FL3") (pin "2") (pinfunction "2_2") (pintype "passive"))
      (node (ref "U1") (pin "W12") (pinfunction "VDDA_CORE_USB_W12") (pintype "power_in"))
    )
    (net (code "24") (name "VDDA_PLL0") (class "Default")
      (node (ref "C65") (pin "1") (pinfunction "1_1") (pintype "passive"))
      (node (ref "C66") (pin "1") (pinfunction "1_1") (pintype "passive"))
      (node (ref "C67") (pin "1") (pinfunction "1_1") (pintype "passive"))
      (node (ref "FL5") (pin "1") (pinfunction "1_1") (pintype "passive"))
      (node (ref "U1") (pin "U11") (pinfunction "VDDA_PLL0_U11") (pintype "power_in"))
    )
    (net (code "25") (name "VDDA_PLL1") (class "Default")
      (node (ref "C71") (pin "1") (pinfunction "1_1") (pintype "passive"))
      (node (ref "C72") (pin "1") (pinfunction "1_1") (pintype "passive"))
      (node (ref "C73") (pin "1") (pinfunction "1_1") (pintype "passive"))
      (node (ref "FL8") (pin "1") (pinfunction "1_1") (pintype "passive"))
      (node (ref "U1") (pin "U15") (pinfunction "VDDA_PLL1_U15") (pintype "power_in"))
    )
    (net (code "26") (name "VDDA_PLL2") (class "Default")
      (node (ref "C80") (pin "1") (pinfunction "1_1") (pintype "passive"))
      (node (ref "C81") (pin "1") (pinfunction "1_1") (pintype "passive"))
      (node (ref "C82") (pin "1") (pinfunction "1_1") (pintype "passive"))
      (node (ref "FL12") (pin "1") (pinfunction "1_1") (pintype "passive"))
      (node (ref "U1") (pin "L14") (pinfunction "VDDA_PLL2_L14") (pintype "power_in"))
    )
    (net (code "27") (name "VDDR_CORE") (class "Default")
      (node (ref "FL9") (pin "2") (pinfunction "2_2") (pintype "passive"))
      (node (ref "U1") (pin "J12") (pinfunction "VDDR_CORE_J12") (pintype "power_in"))
      (node (ref "U1") (pin "K16") (pinfunction "VDDR_CORE_K16") (pintype "power_in"))
      (node (ref "U1") (pin "N12") (pinfunction "VDDR_CORE_N12") (pintype "power_in"))
      (node (ref "U1") (pin "N14") (pinfunction "VDDR_CORE_N14") (pintype "power_in"))
      (node (ref "U1") (pin "P16") (pinfunction "VDDR_CORE_P16") (pintype "power_in"))
      (node (ref "U1") (pin "R12") (pinfunction "VDDR_CORE_R12") (pintype "power_in"))
      (node (ref "U1") (pin "T10") (pinfunction "VDDR_CORE_T10") (pintype "power_in"))
      (node (ref "U1") (pin "U14") (pinfunction "VDDR_CORE_U14") (pintype "power_in"))
    )
    (net (code "28") (name "VDDSHV_SDIO") (class "Default")
      (node (ref "FL4") (pin "2") (pinfunction "2_2") (pintype "passive"))
    )
    (net (code "29") (name "VDD_1V2") (class "Default")
      (node (ref "U1") (pin "K9") (pinfunction "VDDS_DDR_K9") (pintype "power_in"))
      (node (ref "U1") (pin "L8") (pinfunction "VDDS_DDR_L8") (pintype "power_in"))
      (node (ref "U1") (pin "M9") (pinfunction "VDDS_DDR_C_M9") (pintype "power_in"))
      (node (ref "U1") (pin "P9") (pinfunction "VDDS_DDR_P9") (pintype "power_in"))
      (node (ref "U1") (pin "R8") (pinfunction "VDDS_DDR_R8") (pintype "power_in"))
    )
    (net (code "30") (name "VDD_CANUART") (class "Default")
      (node (ref "C83") (pin "1") (pinfunction "1_1") (pintype "passive"))
      (node (ref "C84") (pin "1") (pinfunction "1_1") (pintype "passive"))
      (node (ref "C85") (pin "1") (pinfunction "1_1") (pintype "passive"))
      (node (ref "FL11") (pin "2") (pinfunction "2_2") (pintype "passive"))
      (node (ref "U1") (pin "F8") (pinfunction "VDD_CANUART_F8") (pintype "power_in"))
    )
    (net (code "31") (name "VPP_1V8") (class "Default")
      (node (ref "U1") (pin "J8") (pinfunction "VPP_J8") (pintype "power_in"))
    )
  )
)
